# Sheet2.net
KiCad netlist of a schematic drawn in Altium Designer
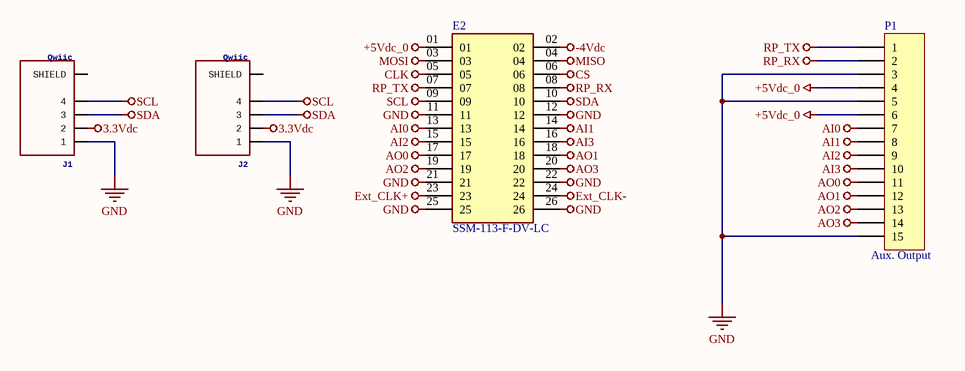
[diagram p0: Sheet2.SchDoc]

(export (version "E")
  (design (tool "Eeschema 10.0.6"))
  (components
    (comp (ref "E2")
      (value "SSM-113-F-DV-LC")
      (footprint "SAMTEC_SSM-113-F-DV-LC:SAMTEC_SSM-113-F-DV-LC")
      (libsource (lib "SSM-113-F-DV-LC") (part "SSM-113-F-DV-LC"))
    )
    (comp (ref "J1")
      (value "Qwiic")
      (footprint "4P RIGHT")
      (fields (field (name "MP") "SM04B-SRSS-TB(LF)(SN)") (field (name "MF") "JST Sales"))
      (libsource (lib "SM04B-SRSS-TB_LF__SN") (part "SM04B-SRSS-TB(LF)(SN)"))
    )
    (comp (ref "J2")
      (value "Qwiic")
      (footprint "4P RIGHT")
      (fields (field (name "MP") "SM04B-SRSS-TB(LF)(SN)") (field (name "MF") "JST Sales"))
      (libsource (lib "SM04B-SRSS-TB_LF__SN") (part "SM04B-SRSS-TB(LF)(SN)"))
    )
    (comp (ref "P1")
      (value "Aux. Output")
      (footprint "15P RIGHT")
      (description "Header, 15-Pin")
      (fields (field (name "PUBLISHER") "Altium Limited"))
      (libsource (lib "Miscellaneous Connectors") (part "Header 15"))
    )
  )
  (nets
    (net (code "1") (name "+5Vdc_0") (class "Default")
      (node (ref "E2") (pin "01") (pinfunction "01_01") (pintype "passive"))
      (node (ref "P1") (pin "4") (pinfunction "4_4") (pintype "passive"))
      (node (ref "P1") (pin "6") (pinfunction "6_6") (pintype "passive"))
    )
    (net (code "2") (name "-4Vdc") (class "Default")
      (node (ref "E2") (pin "02") (pinfunction "02_02") (pintype "passive"))
    )
    (net (code "3") (name "3.3Vdc") (class "Default")
      (node (ref "J1") (pin "2") (pinfunction "2_2") (pintype "passive"))
      (node (ref "J2") (pin "2") (pinfunction "2_2") (pintype "passive"))
    )
    (net (code "4") (name "AI0") (class "Default")
      (node (ref "E2") (pin "13") (pinfunction "13_13") (pintype "passive"))
      (node (ref "P1") (pin "7") (pinfunction "7_7") (pintype "passive"))
    )
    (net (code "5") (name "AI1") (class "Default")
      (node (ref "E2") (pin "14") (pinfunction "14_14") (pintype "passive"))
      (node (ref "P1") (pin "8") (pinfunction "8_8") (pintype "passive"))
    )
    (net (code "6") (name "AI2") (class "Default")
      (node (ref "E2") (pin "15") (pinfunction "15_15") (pintype "passive"))
      (node (ref "P1") (pin "9") (pinfunction "9_9") (pintype "passive"))
    )
    (net (code "7") (name "AI3") (class "Default")
      (node (ref "E2") (pin "16") (pinfunction "16_16") (pintype "passive"))
      (node (ref "P1") (pin "10") (pinfunction "10_10") (pintype "passive"))
    )
    (net (code "8") (name "AO0") (class "Default")
      (node (ref "E2") (pin "17") (pinfunction "17_17") (pintype "passive"))
      (node (ref "P1") (pin "11") (pinfunction "11_11") (pintype "passive"))
    )
    (net (code "9") (name "AO1") (class "Default")
      (node (ref "E2") (pin "18") (pinfunction "18_18") (pintype "passive"))
      (node (ref "P1") (pin "12") (pinfunction "12_12") (pintype "passive"))
    )
    (net (code "10") (name "AO2") (class "Default")
      (node (ref "E2") (pin "19") (pinfunction "19_19") (pintype "passive"))
      (node (ref "P1") (pin "13") (pinfunction "13_13") (pintype "passive"))
    )
    (net (code "11") (name "AO3") (class "Default")
      (node (ref "E2") (pin "20") (pinfunction "20_20") (pintype "passive"))
      (node (ref "P1") (pin "14") (pinfunction "14_14") (pintype "passive"))
    )
    (net (code "12") (name "CLK") (class "Default")
      (node (ref "E2") (pin "05") (pinfunction "05_05") (pintype "passive"))
    )
    (net (code "13") (name "CS") (class "Default")
      (node (ref "E2") (pin "06") (pinfunction "06_06") (pintype "passive"))
    )
    (net (code "14") (name "Ext_CLK+") (class "Default")
      (node (ref "E2") (pin "23") (pinfunction "23_23") (pintype "passive"))
    )
    (net (code "15") (name "Ext_CLK-") (class "Default")
      (node (ref "E2") (pin "24") (pinfunction "24_24") (pintype "passive"))
    )
    (net (code "16") (name "GND") (class "Default")
      (node (ref "E2") (pin "11") (pinfunction "11_11") (pintype "passive"))
      (node (ref "E2") (pin "12") (pinfunction "12_12") (pintype "passive"))
      (node (ref "E2") (pin "21") (pinfunction "21_21") (pintype "passive"))
      (node (ref "E2") (pin "22") (pinfunction "22_22") (pintype "passive"))
      (node (ref "E2") (pin "25") (pinfunction "25_25") (pintype "passive"))
      (node (ref "E2") (pin "26") (pinfunction "26_26") (pintype "passive"))
      (node (ref "J1") (pin "1") (pinfunction "1_1") (pintype "passive"))
      (node (ref "J2") (pin "1") (pinfunction "1_1") (pintype "passive"))
      (node (ref "P1") (pin "15") (pinfunction "15_15") (pintype "passive"))
      (node (ref "P1") (pin "3") (pinfunction "3_3") (pintype "passive"))
      (node (ref "P1") (pin "5") (pinfunction "5_5") (pintype "passive"))
    )
    (net (code "17") (name "MISO") (class "Default")
      (node (ref "E2") (pin "04") (pinfunction "04_04") (pintype "passive"))
    )
    (net (code "18") (name "MOSI") (class "Default")
      (node (ref "E2") (pin "03") (pinfunction "03_03") (pintype "passive"))
    )
    (net (code "19") (name "RP_RX") (class "Default")
      (node (ref "E2") (pin "08") (pinfunction "08_08") (pintype "passive"))
      (node (ref "P1") (pin "2") (pinfunction "2_2") (pintype "passive"))
    )
    (net (code "20") (name "RP_TX") (class "Default")
      (node (ref "E2") (pin "07") (pinfunction "07_07") (pintype "passive"))
      (node (ref "P1") (pin "1") (pinfunction "1_1") (pintype "passive"))
    )
    (net (code "21") (name "SCL") (class "Default")
      (node (ref "E2") (pin "09") (pinfunction "09_09") (pintype "passive"))
      (node (ref "J1") (pin "4") (pinfunction "4_4") (pintype "passive"))
      (node (ref "J2") (pin "4") (pinfunction "4_4") (pintype "passive"))
    )
    (net (code "22") (name "SDA") (class "Default")
      (node (ref "E2") (pin "10") (pinfunction "10_10") (pintype "passive"))
      (node (ref "J1") (pin "3") (pinfunction "3_3") (pintype "passive"))
      (node (ref "J2") (pin "3") (pinfunction "3_3") (pintype "passive"))
    )
    (net (code "23") (name "unconnected-(J1-SHIELD-PadS1_S2)") (class "Default")
      (node (ref "J1") (pin "S1_S2") (pinfunction "SHIELD_S1_S2") (pintype "passive"))
    )
    (net (code "24") (name "unconnected-(J2-SHIELD-PadS1_S2)") (class "Default")
      (node (ref "J2") (pin "S1_S2") (pinfunction "SHIELD_S1_S2") (pintype "passive"))
    )
  )
)
